# Williams_Avalanche_Pulser.net
KiCad netlist of a schematic drawn in EAGLE
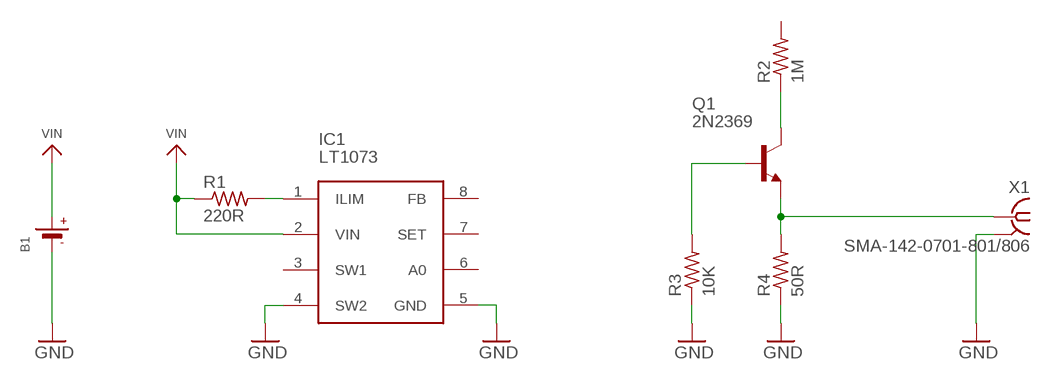
[diagram p0: schematic, sheet 1]

(export (version "E")
  (design (tool "Eeschema 10.0.6"))
  (components
    (comp (ref "B1")
      (value "BATTERYCR1220_SMT")
      (footprint "eagle-import:CR1220")
      (libsource (lib "eagle-import") (part "BATTERYCR1220_SMT"))
    )
    (comp (ref "IC1")
      (value "LT1073")
      (footprint "eagle-import:SOIC8")
      (libsource (lib "eagle-import") (part "LT1073"))
    )
    (comp (ref "Q1")
      (value "2N2369")
      (footprint "eagle-import:TO18")
      (libsource (lib "eagle-import") (part "2N2369"))
    )
    (comp (ref "R1")
      (value "220R")
      (footprint "eagle-import:R0805")
      (libsource (lib "eagle-import") (part "R-US_R0805"))
    )
    (comp (ref "R2")
      (value "1M")
      (footprint "eagle-import:R0805")
      (libsource (lib "eagle-import") (part "R-US_R0805"))
    )
    (comp (ref "R3")
      (value "10K")
      (footprint "eagle-import:R0805")
      (libsource (lib "eagle-import") (part "R-US_R0805"))
    )
    (comp (ref "R4")
      (value "50R")
      (footprint "eagle-import:R0805")
      (libsource (lib "eagle-import") (part "R-US_R0805"))
    )
    (comp (ref "X1")
      (value "SMA-142-0701-801/806")
      (footprint "eagle-import:J502-ND-142-0701-801_806")
      (fields (field (name "MF") "JOHNSON COMPONENTS") (field (name "MPN") "142-0701-801"))
      (libsource (lib "eagle-import") (part "SMA-142-0701-801/806"))
    )
  )
  (nets
    (net (code "1") (name "GND") (class "Default")
      (node (ref "B1") (pin "-") (pinfunction "-_-") (pintype "passive"))
      (node (ref "IC1") (pin "4") (pinfunction "SW2_4") (pintype "bidirectional"))
      (node (ref "IC1") (pin "5") (pinfunction "GND_5") (pintype "bidirectional"))
      (node (ref "R3") (pin "1") (pinfunction "1_1") (pintype "passive"))
      (node (ref "R4") (pin "1") (pinfunction "1_1") (pintype "passive"))
      (node (ref "X1") (pin "G@1") (pinfunction "2_G@1") (pintype "passive"))
      (node (ref "X1") (pin "G@2") (pinfunction "2_G@2") (pintype "passive"))
      (node (ref "X1") (pin "G@3") (pinfunction "2_G@3") (pintype "passive"))
      (node (ref "X1") (pin "G@4") (pinfunction "2_G@4") (pintype "passive"))
    )
    (net (code "2") (name "Net-(IC1-ILIM)") (class "Default")
      (node (ref "IC1") (pin "1") (pinfunction "ILIM_1") (pintype "bidirectional"))
      (node (ref "R1") (pin "2") (pinfunction "2_2") (pintype "passive"))
    )
    (net (code "3") (name "Net-(Q1-B)") (class "Default")
      (node (ref "Q1") (pin "2") (pinfunction "B_2") (pintype "passive"))
      (node (ref "R3") (pin "2") (pinfunction "2_2") (pintype "passive"))
    )
    (net (code "4") (name "Net-(Q1-C)") (class "Default")
      (node (ref "Q1") (pin "3") (pinfunction "C_3") (pintype "passive"))
      (node (ref "R2") (pin "1") (pinfunction "1_1") (pintype "passive"))
    )
    (net (code "5") (name "Net-(Q1-E)") (class "Default")
      (node (ref "Q1") (pin "1") (pinfunction "E_1") (pintype "passive"))
      (node (ref "R4") (pin "2") (pinfunction "2_2") (pintype "passive"))
      (node (ref "X1") (pin "1") (pinfunction "1_1") (pintype "passive"))
    )
    (net (code "6") (name "VIN") (class "Default")
      (node (ref "B1") (pin "+$1") (pinfunction "+_+$1") (pintype "passive"))
      (node (ref "IC1") (pin "2") (pinfunction "VIN_2") (pintype "bidirectional"))
      (node (ref "R1") (pin "1") (pinfunction "1_1") (pintype "passive"))
    )
    (net (code "7") (name "unconnected-(IC1-A0-Pad6)") (class "Default")
      (node (ref "IC1") (pin "6") (pinfunction "A0_6") (pintype "bidirectional"))
    )
    (net (code "8") (name "unconnected-(IC1-FB-Pad8)") (class "Default")
      (node (ref "IC1") (pin "8") (pinfunction "FB_8") (pintype "bidirectional"))
    )
    (net (code "9") (name "unconnected-(IC1-SET-Pad7)") (class "Default")
      (node (ref "IC1") (pin "7") (pinfunction "SET_7") (pintype "bidirectional"))
    )
    (net (code "10") (name "unconnected-(IC1-SW1-Pad3)") (class "Default")
      (node (ref "IC1") (pin "3") (pinfunction "SW1_3") (pintype "bidirectional"))
    )
    (net (code "11") (name "unconnected-(R2-Pad2)") (class "Default")
      (node (ref "R2") (pin "2") (pinfunction "2_2") (pintype "passive"))
    )
  )
)
